# Trefferzonenmodul.net
KiCad netlist of a schematic drawn in EAGLE
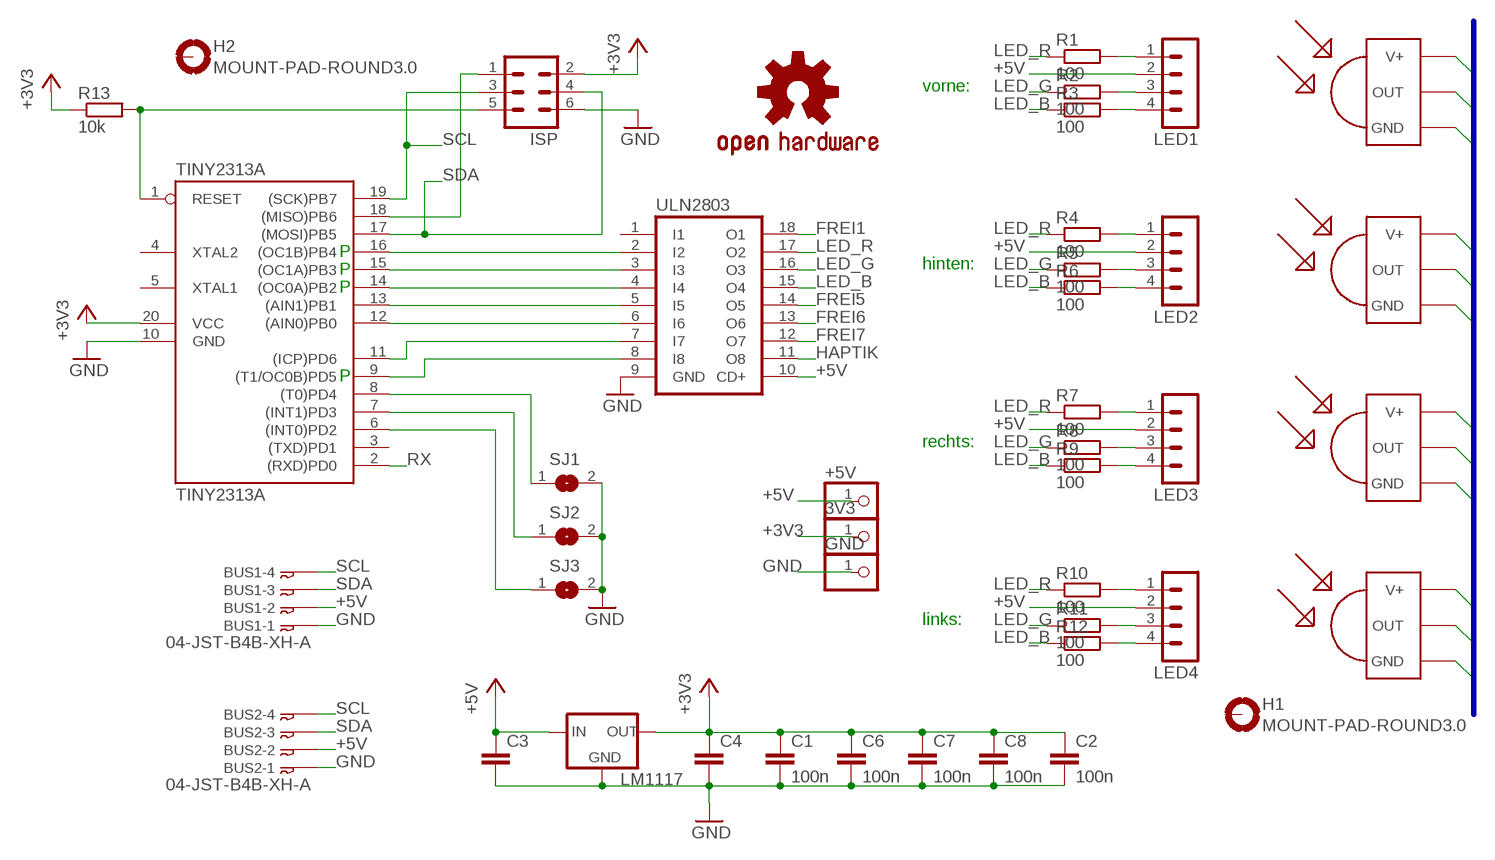
[diagram p0: schematic, sheet 1]

(export (version "E")
  (design (tool "Eeschema 10.0.6"))
  (components
    (comp (ref "+5V")
      (value "PINHD-1X1")
      (footprint "eagle-import:1X01")
      (libsource (lib "eagle-import") (part "PINHD-1X1"))
    )
    (comp (ref "3V3")
      (value "PINHD-1X1")
      (footprint "eagle-import:1X01")
      (libsource (lib "eagle-import") (part "PINHD-1X1"))
    )
    (comp (ref "BUS1")
      (value "04-JST-B4B-XH-A")
      (footprint "eagle-import:B4B-XH")
      (libsource (lib "eagle-import") (part "04-JST-B4B-XH-A"))
    )
    (comp (ref "BUS2")
      (value "04-JST-B4B-XH-A")
      (footprint "eagle-import:B4B-XH")
      (libsource (lib "eagle-import") (part "04-JST-B4B-XH-A"))
    )
    (comp (ref "C1")
      (value "100n")
      (footprint "eagle-import:C0805")
      (libsource (lib "eagle-import") (part "C-EUC0805"))
    )
    (comp (ref "C2")
      (value "100n")
      (footprint "eagle-import:C0805")
      (libsource (lib "eagle-import") (part "C-EUC0805"))
    )
    (comp (ref "C3")
      (value "C-EUCAP_UNIVERSAL")
      (footprint "eagle-import:C1808")
      (libsource (lib "eagle-import") (part "C-EUCAP_UNIVERSAL"))
    )
    (comp (ref "C4")
      (value "C-EUCAP_UNIVERSAL")
      (footprint "eagle-import:C1808")
      (libsource (lib "eagle-import") (part "C-EUCAP_UNIVERSAL"))
    )
    (comp (ref "C6")
      (value "100n")
      (footprint "eagle-import:C0805")
      (libsource (lib "eagle-import") (part "C-EUC0805"))
    )
    (comp (ref "C7")
      (value "100n")
      (footprint "eagle-import:C0805")
      (libsource (lib "eagle-import") (part "C-EUC0805"))
    )
    (comp (ref "C8")
      (value "100n")
      (footprint "eagle-import:C0805")
      (libsource (lib "eagle-import") (part "C-EUC0805"))
    )
    (comp (ref "GND")
      (value "PINHD-1X1")
      (footprint "eagle-import:1X01")
      (libsource (lib "eagle-import") (part "PINHD-1X1"))
    )
    (comp (ref "H1")
      (value "MOUNT-PAD-ROUND3.0")
      (footprint "eagle-import:3,0-PAD")
      (libsource (lib "eagle-import") (part "MOUNT-PAD-ROUND3.0"))
    )
    (comp (ref "H2")
      (value "MOUNT-PAD-ROUND3.0")
      (footprint "eagle-import:3,0-PAD")
      (libsource (lib "eagle-import") (part "MOUNT-PAD-ROUND3.0"))
    )
    (comp (ref "ISP")
      (value "MA03-2")
      (footprint "eagle-import:MA03-2")
      (libsource (lib "eagle-import") (part "MA03-2"))
    )
    (comp (ref "LED1")
      (value "MA04-1")
      (footprint "eagle-import:MA04-1")
      (libsource (lib "eagle-import") (part "MA04-1"))
    )
    (comp (ref "LED2")
      (value "MA04-1")
      (footprint "eagle-import:MA04-1")
      (libsource (lib "eagle-import") (part "MA04-1"))
    )
    (comp (ref "LED3")
      (value "MA04-1")
      (footprint "eagle-import:MA04-1")
      (libsource (lib "eagle-import") (part "MA04-1"))
    )
    (comp (ref "LED4")
      (value "MA04-1")
      (footprint "eagle-import:MA04-1")
      (libsource (lib "eagle-import") (part "MA04-1"))
    )
    (comp (ref "LM1117")
      (value "V_REG_MIC2920")
      (footprint "eagle-import:SOT223")
      (libsource (lib "eagle-import") (part "V_REG_MIC2920"))
    )
    (comp (ref "LOGO2")
      (value "OSHW-LOGOM")
      (footprint "eagle-import:OSHW-LOGO-M")
      (libsource (lib "eagle-import") (part "OSHW-LOGOM"))
    )
    (comp (ref "R1")
      (value "100")
      (footprint "eagle-import:R0805")
      (libsource (lib "eagle-import") (part "R-EU_R0805"))
    )
    (comp (ref "R2")
      (value "100")
      (footprint "eagle-import:R0805")
      (libsource (lib "eagle-import") (part "R-EU_R0805"))
    )
    (comp (ref "R3")
      (value "100")
      (footprint "eagle-import:R0805")
      (libsource (lib "eagle-import") (part "R-EU_R0805"))
    )
    (comp (ref "R4")
      (value "100")
      (footprint "eagle-import:R0805")
      (libsource (lib "eagle-import") (part "R-EU_R0805"))
    )
    (comp (ref "R5")
      (value "100")
      (footprint "eagle-import:R0805")
      (libsource (lib "eagle-import") (part "R-EU_R0805"))
    )
    (comp (ref "R6")
      (value "100")
      (footprint "eagle-import:R0805")
      (libsource (lib "eagle-import") (part "R-EU_R0805"))
    )
    (comp (ref "R7")
      (value "100")
      (footprint "eagle-import:R0805")
      (libsource (lib "eagle-import") (part "R-EU_R0805"))
    )
    (comp (ref "R8")
      (value "100")
      (footprint "eagle-import:R0805")
      (libsource (lib "eagle-import") (part "R-EU_R0805"))
    )
    (comp (ref "R9")
      (value "100")
      (footprint "eagle-import:R0805")
      (libsource (lib "eagle-import") (part "R-EU_R0805"))
    )
    (comp (ref "R10")
      (value "100")
      (footprint "eagle-import:R0805")
      (libsource (lib "eagle-import") (part "R-EU_R0805"))
    )
    (comp (ref "R11")
      (value "100")
      (footprint "eagle-import:R0805")
      (libsource (lib "eagle-import") (part "R-EU_R0805"))
    )
    (comp (ref "R12")
      (value "100")
      (footprint "eagle-import:R0805")
      (libsource (lib "eagle-import") (part "R-EU_R0805"))
    )
    (comp (ref "R13")
      (value "10k")
      (footprint "eagle-import:R0805")
      (libsource (lib "eagle-import") (part "R-EU_R0805"))
    )
    (comp (ref "SJ1") (value "SJ") (footprint "eagle-import:SJ") (libsource (lib "eagle-import") (part "SJ")))
    (comp (ref "SJ2") (value "SJ") (footprint "eagle-import:SJ") (libsource (lib "eagle-import") (part "SJ")))
    (comp (ref "SJ3") (value "SJ") (footprint "eagle-import:SJ") (libsource (lib "eagle-import") (part "SJ")))
    (comp (ref "TINY2313A")
      (value "TINY2313A")
      (footprint "eagle-import:SO20LVERSTUMMELT")
      (libsource (lib "eagle-import") (part "TINY2313A"))
    )
    (comp (ref "U$1")
      (value "TSOP1838")
      (footprint "eagle-import:TSOP18XX")
      (libsource (lib "eagle-import") (part "TSOP1838"))
    )
    (comp (ref "U$2")
      (value "TSOP1838")
      (footprint "eagle-import:TSOP18XX")
      (libsource (lib "eagle-import") (part "TSOP1838"))
    )
    (comp (ref "U$3")
      (value "TSOP1838")
      (footprint "eagle-import:TSOP18XX")
      (libsource (lib "eagle-import") (part "TSOP1838"))
    )
    (comp (ref "U$4")
      (value "TSOP1838")
      (footprint "eagle-import:TSOP18XX")
      (libsource (lib "eagle-import") (part "TSOP1838"))
    )
    (comp (ref "ULN2803")
      (value "ULN2803ASO18")
      (footprint "eagle-import:SO18W")
      (libsource (lib "eagle-import") (part "ULN2803ASO18"))
    )
  )
  (nets
    (net (code "1") (name "+3V3") (class "Default")
      (node (ref "3V3") (pin "1") (pinfunction "1_1") (pintype "passive"))
      (node (ref "C1") (pin "1") (pinfunction "1_1") (pintype "passive"))
      (node (ref "C2") (pin "1") (pinfunction "1_1") (pintype "passive"))
      (node (ref "C4") (pin "1") (pinfunction "1_1") (pintype "passive"))
      (node (ref "C6") (pin "1") (pinfunction "1_1") (pintype "passive"))
      (node (ref "C7") (pin "1") (pinfunction "1_1") (pintype "passive"))
      (node (ref "C8") (pin "1") (pinfunction "1_1") (pintype "passive"))
      (node (ref "ISP") (pin "2") (pinfunction "2_2") (pintype "passive"))
      (node (ref "LM1117") (pin "2") (pinfunction "OUT_2") (pintype "passive"))
      (node (ref "LM1117") (pin "4") (pinfunction "OUT_4") (pintype "passive"))
      (node (ref "R13") (pin "1") (pinfunction "1_1") (pintype "passive"))
      (node (ref "TINY2313A") (pin "20") (pinfunction "VCC_20") (pintype "power_in"))
      (node (ref "U$1") (pin "VCC") (pinfunction "V+_VCC") (pintype "bidirectional"))
      (node (ref "U$2") (pin "VCC") (pinfunction "V+_VCC") (pintype "bidirectional"))
      (node (ref "U$3") (pin "VCC") (pinfunction "V+_VCC") (pintype "bidirectional"))
      (node (ref "U$4") (pin "VCC") (pinfunction "V+_VCC") (pintype "bidirectional"))
    )
    (net (code "2") (name "+5V") (class "Default")
      (node (ref "+5V") (pin "1") (pinfunction "1_1") (pintype "passive"))
      (node (ref "BUS1") (pin "P$2") (pinfunction "1_P$2") (pintype "passive"))
      (node (ref "BUS2") (pin "P$2") (pinfunction "1_P$2") (pintype "passive"))
      (node (ref "C3") (pin "1") (pinfunction "1_1") (pintype "passive"))
      (node (ref "LED1") (pin "2") (pinfunction "2_2") (pintype "passive"))
      (node (ref "LED2") (pin "2") (pinfunction "2_2") (pintype "passive"))
      (node (ref "LED3") (pin "2") (pinfunction "2_2") (pintype "passive"))
      (node (ref "LED4") (pin "2") (pinfunction "2_2") (pintype "passive"))
      (node (ref "LM1117") (pin "3") (pinfunction "IN_3") (pintype "input"))
      (node (ref "ULN2803") (pin "10") (pinfunction "CD+_10") (pintype "passive"))
    )
    (net (code "3") (name "/FREI1") (class "Default")
      (node (ref "ULN2803") (pin "18") (pinfunction "O1_18") (pintype "open_collector"))
    )
    (net (code "4") (name "/FREI5") (class "Default")
      (node (ref "ULN2803") (pin "14") (pinfunction "O5_14") (pintype "open_collector"))
    )
    (net (code "5") (name "/FREI6") (class "Default")
      (node (ref "ULN2803") (pin "13") (pinfunction "O6_13") (pintype "open_collector"))
    )
    (net (code "6") (name "/FREI7") (class "Default")
      (node (ref "ULN2803") (pin "12") (pinfunction "O7_12") (pintype "open_collector"))
    )
    (net (code "7") (name "/HAPTIK") (class "Default")
      (node (ref "ULN2803") (pin "11") (pinfunction "O8_11") (pintype "open_collector"))
    )
    (net (code "8") (name "/LED_B") (class "Default")
      (node (ref "R12") (pin "1") (pinfunction "1_1") (pintype "passive"))
      (node (ref "R3") (pin "1") (pinfunction "1_1") (pintype "passive"))
      (node (ref "R6") (pin "1") (pinfunction "1_1") (pintype "passive"))
      (node (ref "R9") (pin "1") (pinfunction "1_1") (pintype "passive"))
      (node (ref "ULN2803") (pin "15") (pinfunction "O4_15") (pintype "open_collector"))
    )
    (net (code "9") (name "/LED_G") (class "Default")
      (node (ref "R11") (pin "1") (pinfunction "1_1") (pintype "passive"))
      (node (ref "R2") (pin "1") (pinfunction "1_1") (pintype "passive"))
      (node (ref "R5") (pin "1") (pinfunction "1_1") (pintype "passive"))
      (node (ref "R8") (pin "1") (pinfunction "1_1") (pintype "passive"))
      (node (ref "ULN2803") (pin "16") (pinfunction "O3_16") (pintype "open_collector"))
    )
    (net (code "10") (name "/LED_R") (class "Default")
      (node (ref "R1") (pin "1") (pinfunction "1_1") (pintype "passive"))
      (node (ref "R10") (pin "1") (pinfunction "1_1") (pintype "passive"))
      (node (ref "R4") (pin "1") (pinfunction "1_1") (pintype "passive"))
      (node (ref "R7") (pin "1") (pinfunction "1_1") (pintype "passive"))
      (node (ref "ULN2803") (pin "17") (pinfunction "O2_17") (pintype "open_collector"))
    )
    (net (code "11") (name "/RX") (class "Default")
      (node (ref "TINY2313A") (pin "2") (pinfunction "(RXD)PD0_2") (pintype "bidirectional"))
      (node (ref "U$1") (pin "OUT") (pinfunction "OUT_OUT") (pintype "bidirectional"))
      (node (ref "U$2") (pin "OUT") (pinfunction "OUT_OUT") (pintype "bidirectional"))
      (node (ref "U$3") (pin "OUT") (pinfunction "OUT_OUT") (pintype "bidirectional"))
      (node (ref "U$4") (pin "OUT") (pinfunction "OUT_OUT") (pintype "bidirectional"))
    )
    (net (code "12") (name "/SCL") (class "Default")
      (node (ref "BUS1") (pin "P$4") (pinfunction "1_P$4") (pintype "passive"))
      (node (ref "BUS2") (pin "P$4") (pinfunction "1_P$4") (pintype "passive"))
      (node (ref "ISP") (pin "3") (pinfunction "3_3") (pintype "passive"))
      (node (ref "TINY2313A") (pin "19") (pinfunction "(SCK)PB7_19") (pintype "bidirectional"))
    )
    (net (code "13") (name "/SDA") (class "Default")
      (node (ref "BUS1") (pin "P$3") (pinfunction "1_P$3") (pintype "passive"))
      (node (ref "BUS2") (pin "P$3") (pinfunction "1_P$3") (pintype "passive"))
      (node (ref "ISP") (pin "4") (pinfunction "4_4") (pintype "passive"))
      (node (ref "TINY2313A") (pin "17") (pinfunction "(MOSI)PB5_17") (pintype "bidirectional"))
    )
    (net (code "14") (name "GND") (class "Default")
      (node (ref "BUS1") (pin "P$1") (pinfunction "1_P$1") (pintype "passive"))
      (node (ref "BUS2") (pin "P$1") (pinfunction "1_P$1") (pintype "passive"))
      (node (ref "C1") (pin "2") (pinfunction "2_2") (pintype "passive"))
      (node (ref "C2") (pin "2") (pinfunction "2_2") (pintype "passive"))
      (node (ref "C3") (pin "2") (pinfunction "2_2") (pintype "passive"))
      (node (ref "C4") (pin "2") (pinfunction "2_2") (pintype "passive"))
      (node (ref "C6") (pin "2") (pinfunction "2_2") (pintype "passive"))
      (node (ref "C7") (pin "2") (pinfunction "2_2") (pintype "passive"))
      (node (ref "C8") (pin "2") (pinfunction "2_2") (pintype "passive"))
      (node (ref "GND") (pin "1") (pinfunction "1_1") (pintype "passive"))
      (node (ref "ISP") (pin "6") (pinfunction "6_6") (pintype "passive"))
      (node (ref "LM1117") (pin "1") (pinfunction "GND_1") (pintype "input"))
      (node (ref "SJ1") (pin "2") (pinfunction "2_2") (pintype "passive"))
      (node (ref "SJ2") (pin "2") (pinfunction "2_2") (pintype "passive"))
      (node (ref "SJ3") (pin "2") (pinfunction "2_2") (pintype "passive"))
      (node (ref "TINY2313A") (pin "10") (pinfunction "GND_10") (pintype "power_in"))
      (node (ref "U$1") (pin "GND") (pinfunction "GND_GND") (pintype "bidirectional"))
      (node (ref "U$2") (pin "GND") (pinfunction "GND_GND") (pintype "bidirectional"))
      (node (ref "U$3") (pin "GND") (pinfunction "GND_GND") (pintype "bidirectional"))
      (node (ref "U$4") (pin "GND") (pinfunction "GND_GND") (pintype "bidirectional"))
      (node (ref "ULN2803") (pin "9") (pinfunction "GND_9") (pintype "power_in"))
    )
    (net (code "15") (name "Net-(LED1-Pad1)") (class "Default")
      (node (ref "LED1") (pin "1") (pinfunction "1_1") (pintype "passive"))
      (node (ref "R1") (pin "2") (pinfunction "2_2") (pintype "passive"))
    )
    (net (code "16") (name "Net-(LED1-Pad3)") (class "Default")
      (node (ref "LED1") (pin "3") (pinfunction "3_3") (pintype "passive"))
      (node (ref "R2") (pin "2") (pinfunction "2_2") (pintype "passive"))
    )
    (net (code "17") (name "Net-(LED1-Pad4)") (class "Default")
      (node (ref "LED1") (pin "4") (pinfunction "4_4") (pintype "passive"))
      (node (ref "R3") (pin "2") (pinfunction "2_2") (pintype "passive"))
    )
    (net (code "18") (name "Net-(LED2-Pad1)") (class "Default")
      (node (ref "LED2") (pin "1") (pinfunction "1_1") (pintype "passive"))
      (node (ref "R4") (pin "2") (pinfunction "2_2") (pintype "passive"))
    )
    (net (code "19") (name "Net-(LED2-Pad3)") (class "Default")
      (node (ref "LED2") (pin "3") (pinfunction "3_3") (pintype "passive"))
      (node (ref "R5") (pin "2") (pinfunction "2_2") (pintype "passive"))
    )
    (net (code "20") (name "Net-(LED2-Pad4)") (class "Default")
      (node (ref "LED2") (pin "4") (pinfunction "4_4") (pintype "passive"))
      (node (ref "R6") (pin "2") (pinfunction "2_2") (pintype "passive"))
    )
    (net (code "21") (name "Net-(LED3-Pad1)") (class "Default")
      (node (ref "LED3") (pin "1") (pinfunction "1_1") (pintype "passive"))
      (node (ref "R7") (pin "2") (pinfunction "2_2") (pintype "passive"))
    )
    (net (code "22") (name "Net-(LED3-Pad3)") (class "Default")
      (node (ref "LED3") (pin "3") (pinfunction "3_3") (pintype "passive"))
      (node (ref "R8") (pin "2") (pinfunction "2_2") (pintype "passive"))
    )
    (net (code "23") (name "Net-(LED3-Pad4)") (class "Default")
      (node (ref "LED3") (pin "4") (pinfunction "4_4") (pintype "passive"))
      (node (ref "R9") (pin "2") (pinfunction "2_2") (pintype "passive"))
    )
    (net (code "24") (name "Net-(LED4-Pad1)") (class "Default")
      (node (ref "LED4") (pin "1") (pinfunction "1_1") (pintype "passive"))
      (node (ref "R10") (pin "2") (pinfunction "2_2") (pintype "passive"))
    )
    (net (code "25") (name "Net-(LED4-Pad3)") (class "Default")
      (node (ref "LED4") (pin "3") (pinfunction "3_3") (pintype "passive"))
      (node (ref "R11") (pin "2") (pinfunction "2_2") (pintype "passive"))
    )
    (net (code "26") (name "Net-(LED4-Pad4)") (class "Default")
      (node (ref "LED4") (pin "4") (pinfunction "4_4") (pintype "passive"))
      (node (ref "R12") (pin "2") (pinfunction "2_2") (pintype "passive"))
    )
    (net (code "27") (name "Net-(TINY2313A-(AIN0)PB0)") (class "Default")
      (node (ref "TINY2313A") (pin "12") (pinfunction "(AIN0)PB0_12") (pintype "bidirectional"))
      (node (ref "ULN2803") (pin "6") (pinfunction "I6_6") (pintype "input"))
    )
    (net (code "28") (name "Net-(TINY2313A-(AIN1)PB1)") (class "Default")
      (node (ref "TINY2313A") (pin "13") (pinfunction "(AIN1)PB1_13") (pintype "bidirectional"))
      (node (ref "ULN2803") (pin "5") (pinfunction "I5_5") (pintype "input"))
    )
    (net (code "29") (name "Net-(TINY2313A-(ICP)PD6)") (class "Default")
      (node (ref "TINY2313A") (pin "11") (pinfunction "(ICP)PD6_11") (pintype "bidirectional"))
      (node (ref "ULN2803") (pin "7") (pinfunction "I7_7") (pintype "input"))
    )
    (net (code "30") (name "Net-(TINY2313A-(INT0)PD2)") (class "Default")
      (node (ref "SJ3") (pin "1") (pinfunction "1_1") (pintype "passive"))
      (node (ref "TINY2313A") (pin "6") (pinfunction "(INT0)PD2_6") (pintype "bidirectional"))
    )
    (net (code "31") (name "Net-(TINY2313A-(INT1)PD3)") (class "Default")
      (node (ref "SJ2") (pin "1") (pinfunction "1_1") (pintype "passive"))
      (node (ref "TINY2313A") (pin "7") (pinfunction "(INT1)PD3_7") (pintype "bidirectional"))
    )
    (net (code "32") (name "Net-(TINY2313A-(MISO)PB6)") (class "Default")
      (node (ref "ISP") (pin "1") (pinfunction "1_1") (pintype "passive"))
      (node (ref "TINY2313A") (pin "18") (pinfunction "(MISO)PB6_18") (pintype "bidirectional"))
    )
    (net (code "33") (name "Net-(TINY2313A-(OC0A)PB2)") (class "Default")
      (node (ref "TINY2313A") (pin "14") (pinfunction "(OC0A)PB2_14") (pintype "bidirectional"))
      (node (ref "ULN2803") (pin "4") (pinfunction "I4_4") (pintype "input"))
    )
    (net (code "34") (name "Net-(TINY2313A-(OC1A)PB3)") (class "Default")
      (node (ref "TINY2313A") (pin "15") (pinfunction "(OC1A)PB3_15") (pintype "bidirectional"))
      (node (ref "ULN2803") (pin "3") (pinfunction "I3_3") (pintype "input"))
    )
    (net (code "35") (name "Net-(TINY2313A-(OC1B)PB4)") (class "Default")
      (node (ref "TINY2313A") (pin "16") (pinfunction "(OC1B)PB4_16") (pintype "bidirectional"))
      (node (ref "ULN2803") (pin "2") (pinfunction "I2_2") (pintype "input"))
    )
    (net (code "36") (name "Net-(TINY2313A-(T0)PD4)") (class "Default")
      (node (ref "SJ1") (pin "1") (pinfunction "1_1") (pintype "passive"))
      (node (ref "TINY2313A") (pin "8") (pinfunction "(T0)PD4_8") (pintype "bidirectional"))
    )
    (net (code "37") (name "Net-(TINY2313A-(T1{slash}OC0B)PD5)") (class "Default")
      (node (ref "TINY2313A") (pin "9") (pinfunction "(T1/OC0B)PD5_9") (pintype "bidirectional"))
      (node (ref "ULN2803") (pin "8") (pinfunction "I8_8") (pintype "input"))
    )
    (net (code "38") (name "Net-(TINY2313A-RESET)") (class "Default")
      (node (ref "ISP") (pin "5") (pinfunction "5_5") (pintype "passive"))
      (node (ref "R13") (pin "2") (pinfunction "2_2") (pintype "passive"))
      (node (ref "TINY2313A") (pin "1") (pinfunction "RESET_1") (pintype "bidirectional"))
    )
    (net (code "39") (name "unconnected-(H1-MOUNT-PadB3,0)") (class "Default")
      (node (ref "H1") (pin "B3,0") (pinfunction "MOUNT_B3,0") (pintype "passive"))
    )
    (net (code "40") (name "unconnected-(H2-MOUNT-PadB3,0)") (class "Default")
      (node (ref "H2") (pin "B3,0") (pinfunction "MOUNT_B3,0") (pintype "passive"))
    )
    (net (code "41") (name "unconnected-(TINY2313A-(TXD)PD1-Pad3)") (class "Default")
      (node (ref "TINY2313A") (pin "3") (pinfunction "(TXD)PD1_3") (pintype "bidirectional"))
    )
    (net (code "42") (name "unconnected-(TINY2313A-XTAL1-Pad5)") (class "Default")
      (node (ref "TINY2313A") (pin "5") (pinfunction "XTAL1_5") (pintype "bidirectional"))
    )
    (net (code "43") (name "unconnected-(TINY2313A-XTAL2-Pad4)") (class "Default")
      (node (ref "TINY2313A") (pin "4") (pinfunction "XTAL2_4") (pintype "bidirectional"))
    )
    (net (code "44") (name "unconnected-(ULN2803-I1-Pad1)") (class "Default")
      (node (ref "ULN2803") (pin "1") (pinfunction "I1_1") (pintype "input"))
    )
  )
)
